# CamAdapter.net
KiCad netlist of a schematic drawn in EAGLE
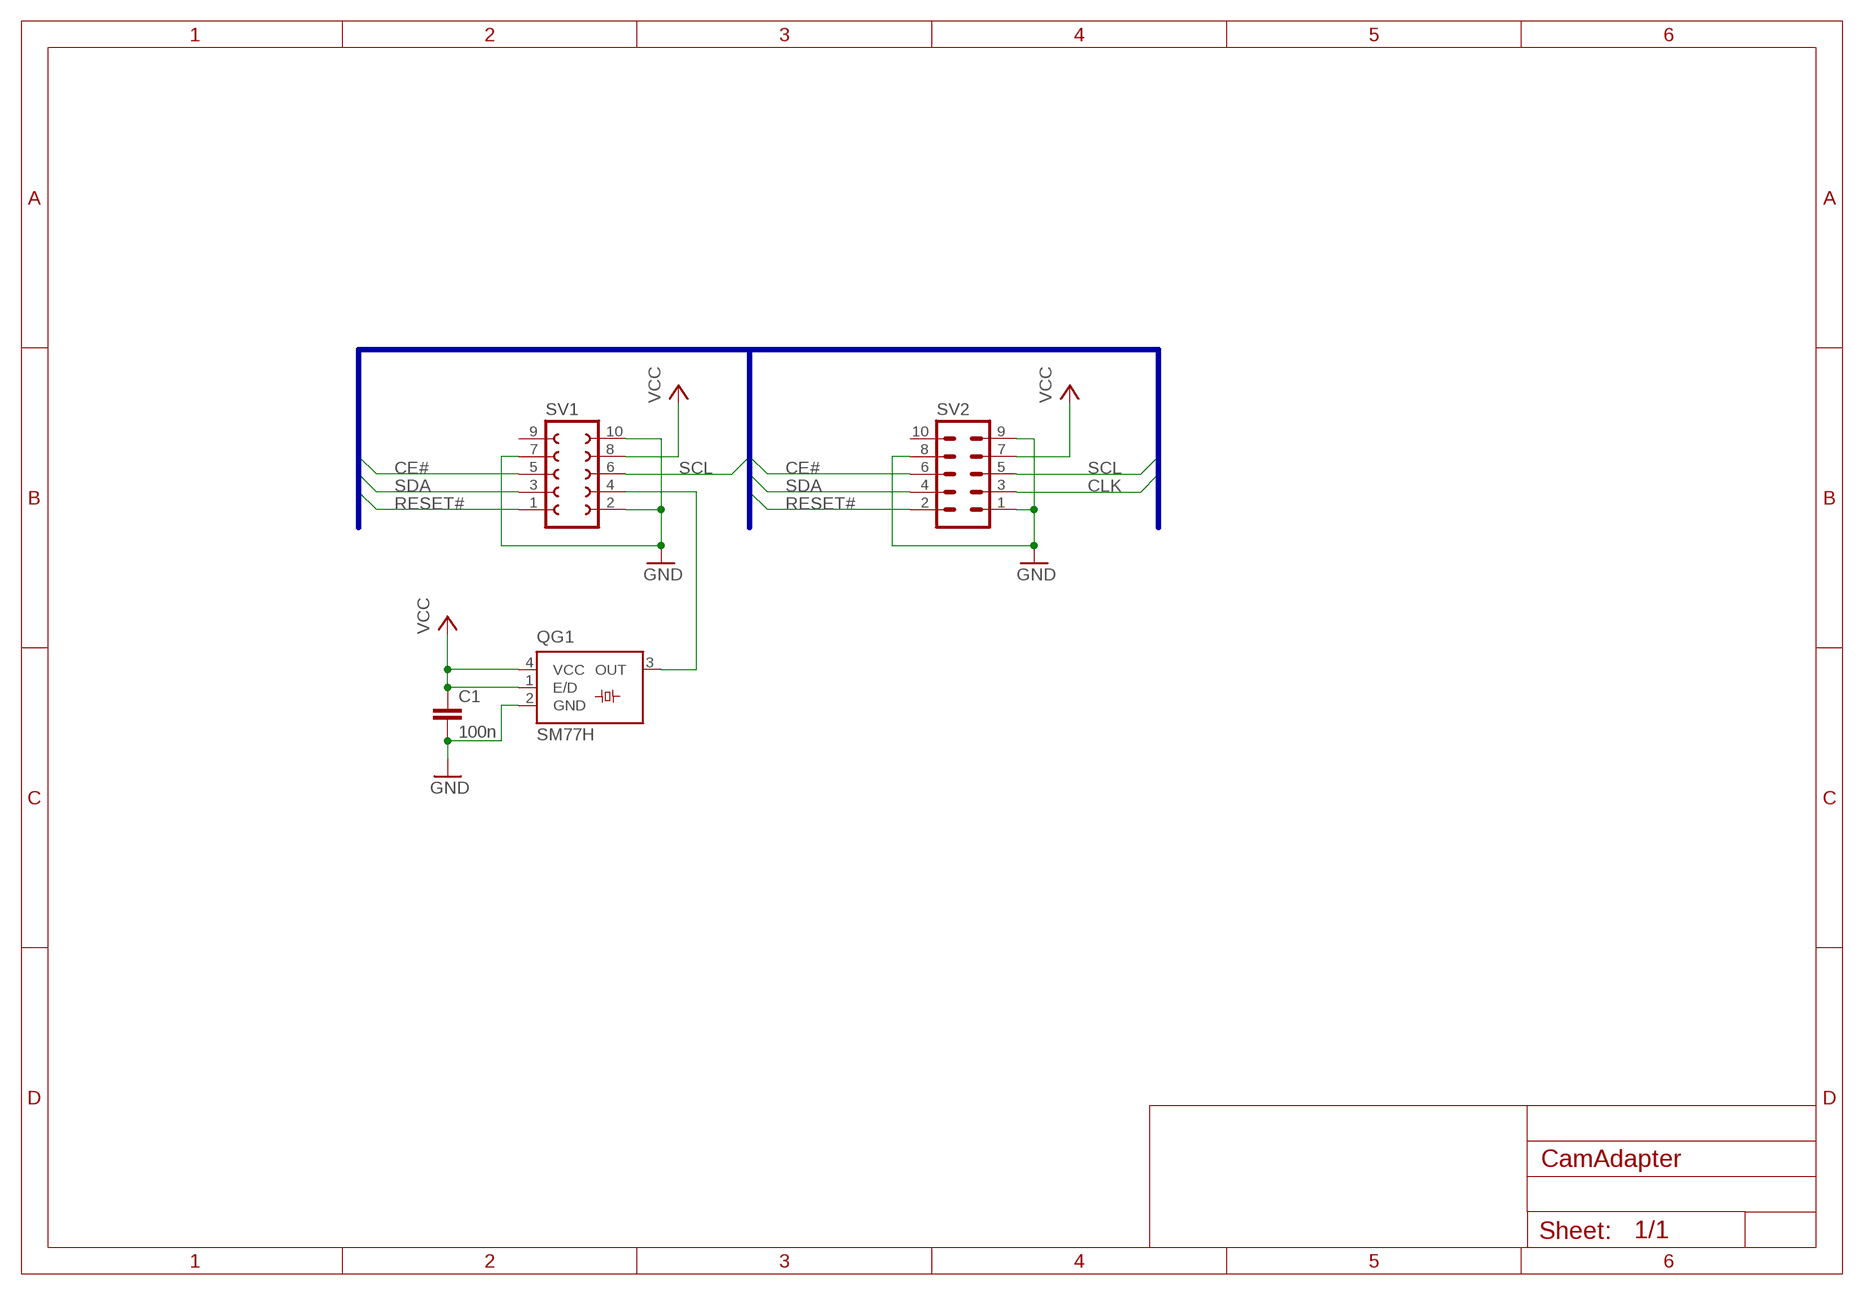
[diagram p0: schematic, sheet 1]

(export (version "E")
  (design (tool "Eeschema 10.0.6"))
  (components
    (comp (ref "C1")
      (value "100n")
      (footprint "eagle-import:C0805")
      (libsource (lib "eagle-import") (part "C-EUC0805"))
    )
    (comp (ref "QG1")
      (value "SM77H")
      (footprint "eagle-import:SM77H")
      (libsource (lib "eagle-import") (part "SM77H"))
    )
    (comp (ref "SV1")
      (value "FE05-2")
      (footprint "eagle-import:FE05-2")
      (libsource (lib "eagle-import") (part "FE05-2"))
    )
    (comp (ref "SV2")
      (value "ML10")
      (footprint "eagle-import:ML10")
      (libsource (lib "eagle-import") (part "ML10"))
    )
  )
  (nets
    (net (code "1") (name "/CE#") (class "Default")
      (node (ref "SV1") (pin "5") (pinfunction "5_5") (pintype "passive"))
      (node (ref "SV2") (pin "6") (pinfunction "6_6") (pintype "passive"))
    )
    (net (code "2") (name "/CLK") (class "Default")
      (node (ref "SV2") (pin "3") (pinfunction "3_3") (pintype "passive"))
    )
    (net (code "3") (name "/RESET#") (class "Default")
      (node (ref "SV1") (pin "1") (pinfunction "1_1") (pintype "passive"))
      (node (ref "SV2") (pin "2") (pinfunction "2_2") (pintype "passive"))
    )
    (net (code "4") (name "/SCL") (class "Default")
      (node (ref "SV1") (pin "6") (pinfunction "6_6") (pintype "passive"))
      (node (ref "SV2") (pin "5") (pinfunction "5_5") (pintype "passive"))
    )
    (net (code "5") (name "/SDA") (class "Default")
      (node (ref "SV1") (pin "3") (pinfunction "3_3") (pintype "passive"))
      (node (ref "SV2") (pin "4") (pinfunction "4_4") (pintype "passive"))
    )
    (net (code "6") (name "GND") (class "Default")
      (node (ref "C1") (pin "2") (pinfunction "2_2") (pintype "passive"))
      (node (ref "QG1") (pin "2") (pinfunction "GND_2") (pintype "power_in"))
      (node (ref "SV1") (pin "10") (pinfunction "10_10") (pintype "passive"))
      (node (ref "SV1") (pin "2") (pinfunction "2_2") (pintype "passive"))
      (node (ref "SV1") (pin "7") (pinfunction "7_7") (pintype "passive"))
      (node (ref "SV2") (pin "1") (pinfunction "1_1") (pintype "passive"))
      (node (ref "SV2") (pin "8") (pinfunction "8_8") (pintype "passive"))
      (node (ref "SV2") (pin "9") (pinfunction "9_9") (pintype "passive"))
    )
    (net (code "7") (name "Net-(QG1-OUT)") (class "Default")
      (node (ref "QG1") (pin "3") (pinfunction "OUT_3") (pintype "output"))
      (node (ref "SV1") (pin "4") (pinfunction "4_4") (pintype "passive"))
    )
    (net (code "8") (name "VCC") (class "Default")
      (node (ref "C1") (pin "1") (pinfunction "1_1") (pintype "passive"))
      (node (ref "QG1") (pin "1") (pinfunction "E/D_1") (pintype "input"))
      (node (ref "QG1") (pin "4") (pinfunction "VCC_4") (pintype "power_in"))
      (node (ref "SV1") (pin "8") (pinfunction "8_8") (pintype "passive"))
      (node (ref "SV2") (pin "7") (pinfunction "7_7") (pintype "passive"))
    )
    (net (code "9") (name "unconnected-(SV1-Pad9)") (class "Default")
      (node (ref "SV1") (pin "9") (pinfunction "9_9") (pintype "passive"))
    )
    (net (code "10") (name "unconnected-(SV2-Pad10)") (class "Default")
      (node (ref "SV2") (pin "10") (pinfunction "10_10") (pintype "passive"))
    )
  )
)
